# usb_shield.net
KiCad netlist of a schematic drawn in EAGLE
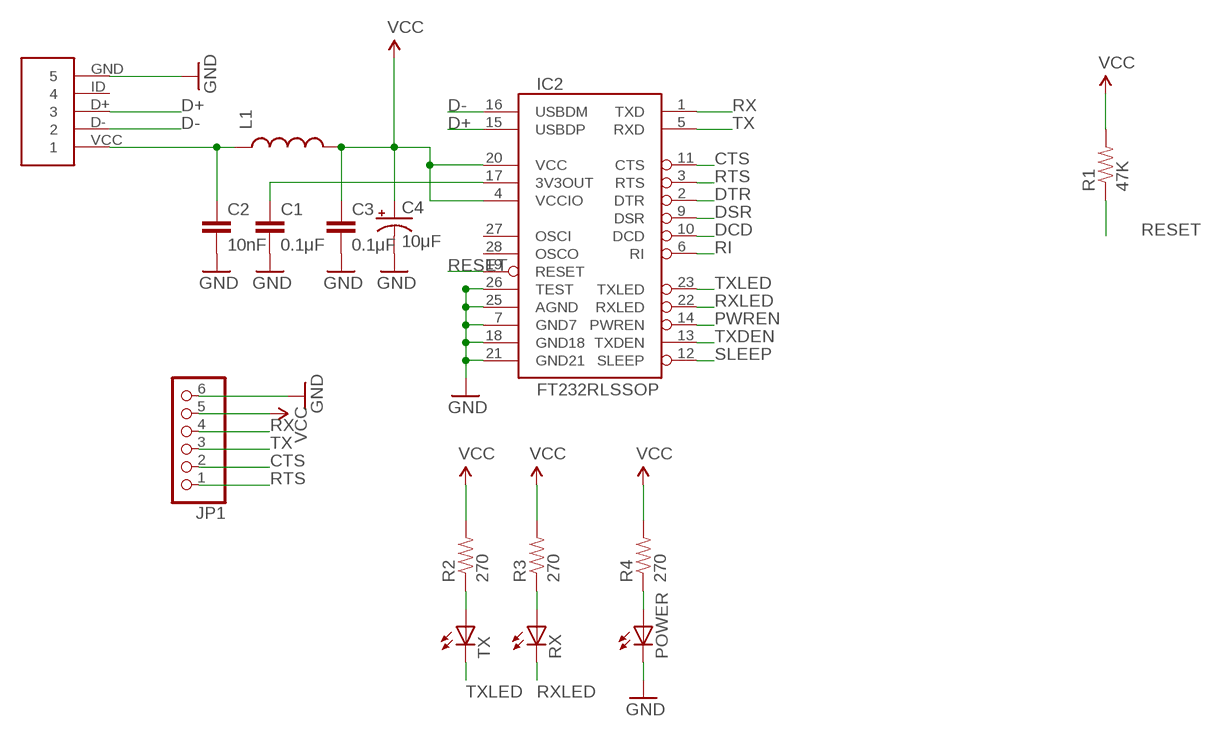
[diagram p0: schematic, sheet 1]

(export (version "E")
  (design (tool "Eeschema 10.0.6"))
  (components
    (comp (ref "C1")
      (value "0.1μF")
      (footprint "eagle-import:0603-CAP")
      (libsource (lib "eagle-import") (part "CAP0603-CAP"))
    )
    (comp (ref "C2")
      (value "10nF")
      (footprint "eagle-import:0603-CAP")
      (libsource (lib "eagle-import") (part "CAP0603-CAP"))
    )
    (comp (ref "C3")
      (value "0.1μF")
      (footprint "eagle-import:0603-CAP")
      (libsource (lib "eagle-import") (part "CAP0603-CAP"))
    )
    (comp (ref "C4")
      (value "10μF")
      (footprint "eagle-import:EIA3216")
      (libsource (lib "eagle-import") (part "CAP_POL1206"))
    )
    (comp (ref "IC2")
      (value "FT232RLSSOP")
      (footprint "eagle-import:SSOP28DB")
      (libsource (lib "eagle-import") (part "FT232RLSSOP"))
    )
    (comp (ref "JP1")
      (value "PINHD-1X6")
      (footprint "eagle-import:1X06")
      (libsource (lib "eagle-import") (part "PINHD-1X6"))
    )
    (comp (ref "L1")
      (value "INDUCTOR0603")
      (footprint "eagle-import:0603")
      (libsource (lib "eagle-import") (part "INDUCTOR0603"))
    )
    (comp (ref "POWER")
      (value "LEDCHIP-LED0805")
      (footprint "eagle-import:CHIP-LED0805")
      (libsource (lib "eagle-import") (part "LEDCHIP-LED0805"))
    )
    (comp (ref "R1")
      (value "47K")
      (footprint "eagle-import:0603-RES")
      (libsource (lib "eagle-import") (part "RESISTOR0603-RES"))
    )
    (comp (ref "R2")
      (value "270")
      (footprint "eagle-import:0603-RES")
      (libsource (lib "eagle-import") (part "RESISTOR0603-RES"))
    )
    (comp (ref "R3")
      (value "270")
      (footprint "eagle-import:0603-RES")
      (libsource (lib "eagle-import") (part "RESISTOR0603-RES"))
    )
    (comp (ref "R4")
      (value "270")
      (footprint "eagle-import:0603-RES")
      (libsource (lib "eagle-import") (part "RESISTOR0603-RES"))
    )
    (comp (ref "RX")
      (value "LEDCHIP-LED0805")
      (footprint "eagle-import:CHIP-LED0805")
      (libsource (lib "eagle-import") (part "LEDCHIP-LED0805"))
    )
    (comp (ref "TX")
      (value "LEDCHIP-LED0805")
      (footprint "eagle-import:CHIP-LED0805")
      (libsource (lib "eagle-import") (part "LEDCHIP-LED0805"))
    )
    (comp (ref "U$1")
      (value "USB-MICRO-B-FEMALE")
      (footprint "eagle-import:USB-MICRO-B-FEMALE")
      (libsource (lib "eagle-import") (part "USB-MICRO-B-FEMALE"))
    )
  )
  (nets
    (net (code "1") (name "/CTS") (class "Default")
      (node (ref "IC2") (pin "11") (pinfunction "CTS_11") (pintype "input"))
      (node (ref "JP1") (pin "2") (pinfunction "2_2") (pintype "passive"))
    )
    (net (code "2") (name "/D+") (class "Default")
      (node (ref "IC2") (pin "15") (pinfunction "USBDP_15") (pintype "bidirectional"))
      (node (ref "U$1") (pin "D+") (pinfunction "3_D+") (pintype "bidirectional"))
    )
    (net (code "3") (name "/D-") (class "Default")
      (node (ref "IC2") (pin "16") (pinfunction "USBDM_16") (pintype "bidirectional"))
      (node (ref "U$1") (pin "D-") (pinfunction "2_D-") (pintype "bidirectional"))
    )
    (net (code "4") (name "/DCD") (class "Default")
      (node (ref "IC2") (pin "10") (pinfunction "DCD_10") (pintype "input"))
    )
    (net (code "5") (name "/DSR") (class "Default")
      (node (ref "IC2") (pin "9") (pinfunction "DSR_9") (pintype "input"))
    )
    (net (code "6") (name "/DTR") (class "Default")
      (node (ref "IC2") (pin "2") (pinfunction "DTR_2") (pintype "output"))
    )
    (net (code "7") (name "/PWREN") (class "Default")
      (node (ref "IC2") (pin "14") (pinfunction "PWREN_14") (pintype "input"))
    )
    (net (code "8") (name "/RESET") (class "Default")
      (node (ref "IC2") (pin "19") (pinfunction "RESET_19") (pintype "input"))
      (node (ref "R1") (pin "1") (pinfunction "1_1") (pintype "passive"))
    )
    (net (code "9") (name "/RI") (class "Default")
      (node (ref "IC2") (pin "6") (pinfunction "RI_6") (pintype "input"))
    )
    (net (code "10") (name "/RTS") (class "Default")
      (node (ref "IC2") (pin "3") (pinfunction "RTS_3") (pintype "output"))
      (node (ref "JP1") (pin "1") (pinfunction "1_1") (pintype "passive"))
    )
    (net (code "11") (name "/RX") (class "Default")
      (node (ref "IC2") (pin "1") (pinfunction "TXD_1") (pintype "output"))
      (node (ref "JP1") (pin "4") (pinfunction "4_4") (pintype "passive"))
    )
    (net (code "12") (name "/RXLED") (class "Default")
      (node (ref "IC2") (pin "22") (pinfunction "RXLED_22") (pintype "input"))
      (node (ref "RX") (pin "C") (pinfunction "C_C") (pintype "passive"))
    )
    (net (code "13") (name "/SLEEP") (class "Default")
      (node (ref "IC2") (pin "12") (pinfunction "SLEEP_12") (pintype "input"))
    )
    (net (code "14") (name "/TX") (class "Default")
      (node (ref "IC2") (pin "5") (pinfunction "RXD_5") (pintype "input"))
      (node (ref "JP1") (pin "3") (pinfunction "3_3") (pintype "passive"))
    )
    (net (code "15") (name "/TXDEN") (class "Default")
      (node (ref "IC2") (pin "13") (pinfunction "TXDEN_13") (pintype "input"))
    )
    (net (code "16") (name "/TXLED") (class "Default")
      (node (ref "IC2") (pin "23") (pinfunction "TXLED_23") (pintype "input"))
      (node (ref "TX") (pin "C") (pinfunction "C_C") (pintype "passive"))
    )
    (net (code "17") (name "GND") (class "Default")
      (node (ref "C1") (pin "2") (pinfunction "2_2") (pintype "passive"))
      (node (ref "C2") (pin "2") (pinfunction "2_2") (pintype "passive"))
      (node (ref "C3") (pin "2") (pinfunction "2_2") (pintype "passive"))
      (node (ref "C4") (pin "C") (pinfunction "-_C") (pintype "passive"))
      (node (ref "IC2") (pin "18") (pinfunction "GND18_18") (pintype "power_in"))
      (node (ref "IC2") (pin "21") (pinfunction "GND21_21") (pintype "power_in"))
      (node (ref "IC2") (pin "25") (pinfunction "AGND_25") (pintype "power_in"))
      (node (ref "IC2") (pin "26") (pinfunction "TEST_26") (pintype "input"))
      (node (ref "IC2") (pin "7") (pinfunction "GND7_7") (pintype "power_in"))
      (node (ref "JP1") (pin "6") (pinfunction "6_6") (pintype "passive"))
      (node (ref "POWER") (pin "C") (pinfunction "C_C") (pintype "passive"))
      (node (ref "U$1") (pin "GND") (pinfunction "5_GND") (pintype "bidirectional"))
    )
    (net (code "18") (name "Net-(IC2-3V3OUT)") (class "Default")
      (node (ref "C1") (pin "1") (pinfunction "1_1") (pintype "passive"))
      (node (ref "IC2") (pin "17") (pinfunction "3V3OUT_17") (pintype "output"))
    )
    (net (code "19") (name "Net-(POWER-PadA)") (class "Default")
      (node (ref "POWER") (pin "A") (pinfunction "A_A") (pintype "passive"))
      (node (ref "R4") (pin "1") (pinfunction "1_1") (pintype "passive"))
    )
    (net (code "20") (name "Net-(R2-Pad1)") (class "Default")
      (node (ref "R2") (pin "1") (pinfunction "1_1") (pintype "passive"))
      (node (ref "TX") (pin "A") (pinfunction "A_A") (pintype "passive"))
    )
    (net (code "21") (name "Net-(R3-Pad1)") (class "Default")
      (node (ref "R3") (pin "1") (pinfunction "1_1") (pintype "passive"))
      (node (ref "RX") (pin "A") (pinfunction "A_A") (pintype "passive"))
    )
    (net (code "22") (name "Net-(U$1-1)") (class "Default")
      (node (ref "C2") (pin "1") (pinfunction "1_1") (pintype "passive"))
      (node (ref "L1") (pin "1") (pinfunction "1_1") (pintype "passive"))
      (node (ref "U$1") (pin "VCC") (pinfunction "1_VCC") (pintype "bidirectional"))
    )
    (net (code "23") (name "VCC") (class "Default")
      (node (ref "C3") (pin "1") (pinfunction "1_1") (pintype "passive"))
      (node (ref "C4") (pin "A") (pinfunction "+_A") (pintype "passive"))
      (node (ref "IC2") (pin "20") (pinfunction "VCC_20") (pintype "power_in"))
      (node (ref "IC2") (pin "4") (pinfunction "VCCIO_4") (pintype "power_in"))
      (node (ref "JP1") (pin "5") (pinfunction "5_5") (pintype "passive"))
      (node (ref "L1") (pin "2") (pinfunction "2_2") (pintype "passive"))
      (node (ref "R1") (pin "2") (pinfunction "2_2") (pintype "passive"))
      (node (ref "R2") (pin "2") (pinfunction "2_2") (pintype "passive"))
      (node (ref "R3") (pin "2") (pinfunction "2_2") (pintype "passive"))
      (node (ref "R4") (pin "2") (pinfunction "2_2") (pintype "passive"))
    )
    (net (code "24") (name "unconnected-(IC2-OSCI-Pad27)") (class "Default")
      (node (ref "IC2") (pin "27") (pinfunction "OSCI_27") (pintype "input"))
    )
    (net (code "25") (name "unconnected-(IC2-OSCO-Pad28)") (class "Default")
      (node (ref "IC2") (pin "28") (pinfunction "OSCO_28") (pintype "output"))
    )
    (net (code "26") (name "unconnected-(U$1-4-PadID)") (class "Default")
      (node (ref "U$1") (pin "ID") (pinfunction "4_ID") (pintype "bidirectional"))
    )
  )
)
